# power_path_control.net
KiCad netlist of a schematic drawn in Altium Designer
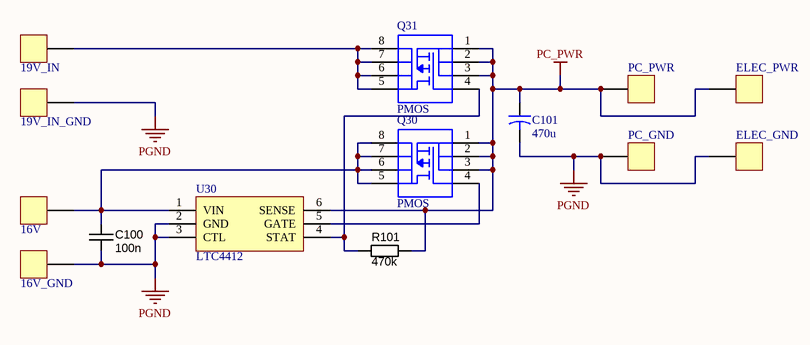
[diagram p0: power_path_control.SchDoc]

(export (version "E")
  (design (tool "Eeschema 10.0.6"))
  (components
    (comp (ref "16V") (value "HEADER-1") (footprint "POWER-PAD-4x3") (libsource (lib "") (part "HEADER-1_1")))
    (comp (ref "16V_GND")
      (value "HEADER-1")
      (footprint "POWER-PAD-4x3")
      (libsource (lib "") (part "HEADER-1_1"))
    )
    (comp (ref "19V_IN")
      (value "HEADER-1")
      (footprint "POWER-PAD-4x3")
      (libsource (lib "") (part "HEADER-1_1"))
    )
    (comp (ref "19V_IN_GND")
      (value "HEADER-1")
      (footprint "POWER-PAD-4x3")
      (libsource (lib "") (part "HEADER-1_1"))
    )
    (comp (ref "C100")
      (value "100n")
      (footprint "CAPC1608X90N")
      (description "Capacitor SMD Cer 10nF 10% 50V X7R 0603")
      (fields (field (name "TOLERANCE") "±10%"))
      (libsource (lib "PBL - Capacitors") (part "CAPC_10n_0603_X7R_50V_10%"))
    )
    (comp (ref "C101")
      (value "470u")
      (footprint "CAPR5-4X5")
      (description "Capacitor")
      (fields (field (name "PUBLISHER") "Altium Limited"))
      (libsource (lib "Miscellaneous Devices") (part "Cap2"))
    )
    (comp (ref "ELEC_GND")
      (value "HEADER-1")
      (footprint "POWER-PAD-4x3")
      (libsource (lib "connectors") (part "HEADER-1"))
    )
    (comp (ref "ELEC_PWR")
      (value "HEADER-1")
      (footprint "POWER-PAD-4x3")
      (libsource (lib "connectors") (part "HEADER-1"))
    )
    (comp (ref "PC_GND")
      (value "HEADER-1")
      (footprint "POWER-PAD-4x3")
      (libsource (lib "connectors") (part "HEADER-1"))
    )
    (comp (ref "PC_PWR")
      (value "HEADER-1")
      (footprint "POWER-PAD-4x3")
      (libsource (lib "connectors") (part "HEADER-1"))
    )
    (comp (ref "Q30") (value "PMOS") (footprint "SO8") (libsource (lib "misc") (part "PMOS")))
    (comp (ref "Q31") (value "PMOS") (footprint "SO8") (libsource (lib "misc") (part "PMOS")))
    (comp (ref "R101")
      (value "470k")
      (footprint "RESC1608N_ZERO")
      (description "Resistor SMD chip 0.0 Ohm 0.1W 0603")
      (fields (field (name "TOLERANCE") "±5%"))
      (libsource (lib "PBL - Resistors") (part "RES_0R_0603"))
    )
    (comp (ref "U30") (value "LTC4412") (footprint "TSOT-23-6") (libsource (lib "digital") (part "LTC4412")))
  )
  (nets
    (net (code "1") (name "Net-(19V_IN-Pad1)") (class "Default")
      (node (ref "19V_IN") (pin "1") (pinfunction "1_1") (pintype "passive"))
      (node (ref "Q31") (pin "5") (pinfunction "5_5") (pintype "passive"))
      (node (ref "Q31") (pin "6") (pinfunction "6_6") (pintype "passive"))
      (node (ref "Q31") (pin "7") (pinfunction "7_7") (pintype "passive"))
      (node (ref "Q31") (pin "8") (pinfunction "8_8") (pintype "passive"))
    )
    (net (code "2") (name "Net-(U30-GATE)") (class "Default")
      (node (ref "Q30") (pin "4") (pinfunction "4_4") (pintype "passive"))
      (node (ref "U30") (pin "5") (pinfunction "GATE_5") (pintype "passive"))
    )
    (net (code "3") (name "Net-(U30-STAT)") (class "Default")
      (node (ref "Q31") (pin "4") (pinfunction "4_4") (pintype "passive"))
      (node (ref "R101") (pin "2") (pinfunction "2_2") (pintype "passive"))
      (node (ref "U30") (pin "4") (pinfunction "STAT_4") (pintype "passive"))
    )
    (net (code "4") (name "Net-(U30-VIN)") (class "Default")
      (node (ref "16V") (pin "1") (pinfunction "1_1") (pintype "passive"))
      (node (ref "C100") (pin "1") (pintype "passive"))
      (node (ref "Q30") (pin "5") (pinfunction "5_5") (pintype "passive"))
      (node (ref "Q30") (pin "6") (pinfunction "6_6") (pintype "passive"))
      (node (ref "Q30") (pin "7") (pinfunction "7_7") (pintype "passive"))
      (node (ref "Q30") (pin "8") (pinfunction "8_8") (pintype "passive"))
      (node (ref "U30") (pin "1") (pinfunction "VIN_1") (pintype "passive"))
    )
    (net (code "5") (name "PC_PWR") (class "Default")
      (node (ref "C101") (pin "1") (pinfunction "1_1") (pintype "passive"))
      (node (ref "ELEC_PWR") (pin "1") (pinfunction "1_1") (pintype "passive"))
      (node (ref "PC_PWR") (pin "1") (pinfunction "1_1") (pintype "passive"))
      (node (ref "Q30") (pin "1") (pinfunction "1_1") (pintype "passive"))
      (node (ref "Q30") (pin "2") (pinfunction "2_2") (pintype "passive"))
      (node (ref "Q30") (pin "3") (pinfunction "3_3") (pintype "passive"))
      (node (ref "Q31") (pin "1") (pinfunction "1_1") (pintype "passive"))
      (node (ref "Q31") (pin "2") (pinfunction "2_2") (pintype "passive"))
      (node (ref "Q31") (pin "3") (pinfunction "3_3") (pintype "passive"))
      (node (ref "R101") (pin "1") (pinfunction "1_1") (pintype "passive"))
      (node (ref "U30") (pin "6") (pinfunction "SENSE_6") (pintype "passive"))
    )
    (net (code "6") (name "PGND") (class "Default")
      (node (ref "16V_GND") (pin "1") (pinfunction "1_1") (pintype "passive"))
      (node (ref "19V_IN_GND") (pin "1") (pinfunction "1_1") (pintype "passive"))
      (node (ref "C100") (pin "2") (pintype "passive"))
      (node (ref "C101") (pin "2") (pinfunction "2_2") (pintype "passive"))
      (node (ref "ELEC_GND") (pin "1") (pinfunction "1_1") (pintype "passive"))
      (node (ref "PC_GND") (pin "1") (pinfunction "1_1") (pintype "passive"))
      (node (ref "U30") (pin "2") (pinfunction "GND_2") (pintype "passive"))
      (node (ref "U30") (pin "3") (pinfunction "CTL_3") (pintype "passive"))
    )
  )
)
